# Schematic_MASTER.net
KiCad netlist of a schematic drawn in Altium Designer
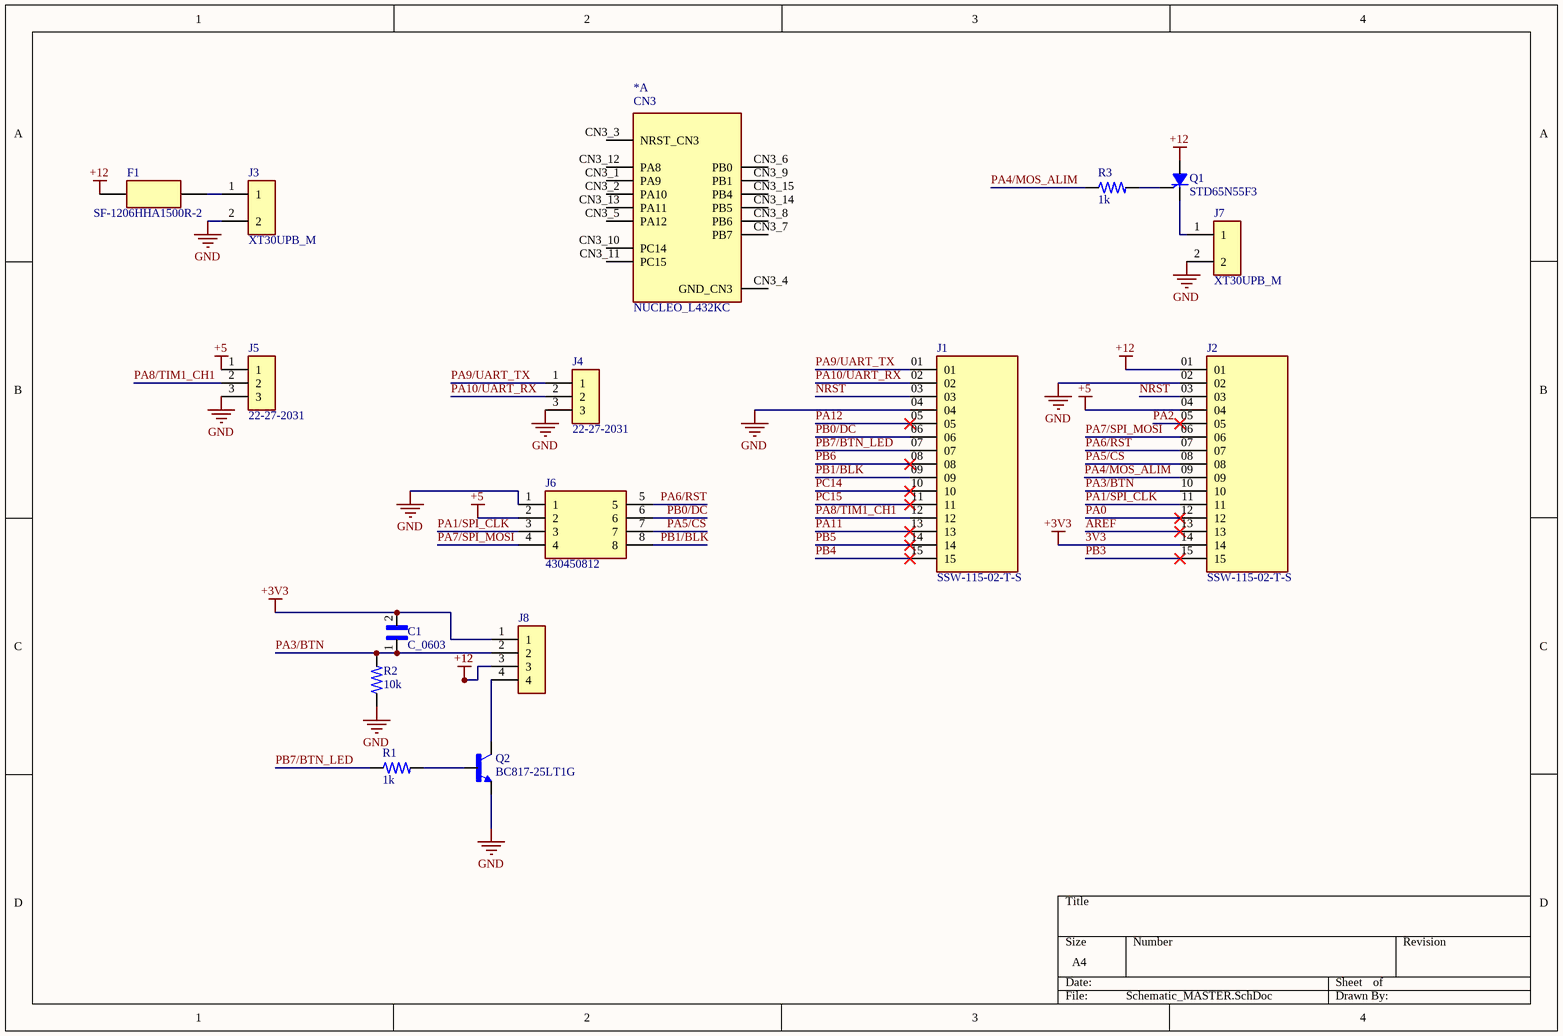
[diagram p0: Schematic_MASTER.SchDoc]

(export (version "E")
  (design (tool "Eeschema 10.0.6"))
  (components
    (comp (ref "*")
      (value "NUCLEO_L432KC")
      (footprint "NUCLEO_L432KC")
      (libsource (lib "Librairy_schematic") (part "NUCLEO_L432KC"))
    )
    (comp (ref "C1")
      (value "C_0603")
      (footprint "C_0603")
      (description "SMD capacitor 0603")
      (libsource (lib "Librairy_schematic") (part "C_0603"))
    )
    (comp (ref "F1")
      (value "SF-1206HHA1500R-2")
      (footprint "SF-1206HHA1500R-2")
      (libsource (lib "Librairy_schematic") (part "SF-1206HHA1500R-2"))
    )
    (comp (ref "J1")
      (value "SSW-115-02-T-S")
      (footprint "SSW-115-02-T-S")
      (libsource (lib "Librairy_schematic") (part "SSW-115-02-T-S"))
    )
    (comp (ref "J2")
      (value "SSW-115-02-T-S")
      (footprint "SSW-115-02-T-S")
      (libsource (lib "Librairy_schematic") (part "SSW-115-02-T-S"))
    )
    (comp (ref "J3")
      (value "XT30UPB_M")
      (footprint "XT30UPB-M")
      (libsource (lib "Librairy_schematic") (part "XT30UPB_M"))
    )
    (comp (ref "J4")
      (value "22-27-2031")
      (footprint "22-27-2031")
      (libsource (lib "Librairy_schematic") (part "22-27-2031"))
    )
    (comp (ref "J5")
      (value "22-27-2031")
      (footprint "22-27-2031")
      (libsource (lib "Librairy_schematic") (part "22-27-2031"))
    )
    (comp (ref "J6")
      (value "430450812")
      (footprint "430450812")
      (libsource (lib "Librairy_schematic") (part "430450812"))
    )
    (comp (ref "J7")
      (value "XT30UPB_M")
      (footprint "XT30UPB-M")
      (libsource (lib "Librairy_schematic") (part "XT30UPB_M"))
    )
    (comp (ref "J8")
      (value "22-27-2041")
      (footprint "22-27-2041")
      (libsource (lib "Librairy_schematic") (part "22-27-2041"))
    )
    (comp (ref "Q1")
      (value "STD65N55F3")
      (footprint "STD65N55F3")
      (libsource (lib "Librairy_schematic") (part "STD65N55F3"))
    )
    (comp (ref "Q2")
      (value "BC817-25LT1G")
      (footprint "SOT_BC817")
      (description "Transistor NPN 45V 0.5A hfe160 SOT23 ¦ ON Semiconductor BC817-25LT1G")
      (fields (field (name "MF") "ON Semiconductor"))
      (libsource (lib "Librairy_schematic") (part "BC817-25LT1G"))
    )
    (comp (ref "R1")
      (value "1k")
      (footprint "R_0603")
      (description "Res 0603")
      (libsource (lib "Librairy_schematic") (part "R_0603"))
    )
    (comp (ref "R2")
      (value "10k")
      (footprint "R_0603")
      (description "Res 0603")
      (libsource (lib "Librairy_schematic") (part "R_0603"))
    )
    (comp (ref "R3")
      (value "1k")
      (footprint "R_0603")
      (description "Res 0603")
      (libsource (lib "Librairy_schematic") (part "R_0603"))
    )
  )
  (nets
    (net (code "1") (name "+3V3") (class "Default")
      (node (ref "C1") (pin "2") (pinfunction "2_2") (pintype "passive"))
      (node (ref "J2") (pin "14") (pinfunction "14_14") (pintype "passive"))
      (node (ref "J8") (pin "1") (pinfunction "1_1") (pintype "passive"))
    )
    (net (code "2") (name "+5") (class "Default")
      (node (ref "J2") (pin "04") (pinfunction "04_04") (pintype "passive"))
      (node (ref "J5") (pin "1") (pinfunction "1_1") (pintype "passive"))
      (node (ref "J6") (pin "2") (pinfunction "2_2") (pintype "passive"))
    )
    (net (code "3") (name "+12") (class "Default")
      (node (ref "F1") (pin "1") (pinfunction "1_1") (pintype "passive"))
      (node (ref "J2") (pin "01") (pinfunction "01_01") (pintype "passive"))
      (node (ref "J8") (pin "3") (pinfunction "3_3") (pintype "passive"))
      (node (ref "Q1") (pin "2") (pinfunction "A_2") (pintype "passive"))
    )
    (net (code "4") (name "/AREF") (class "Default")
      (node (ref "J2") (pin "13") (pinfunction "13_13") (pintype "passive+no_connect"))
    )
    (net (code "5") (name "/NRST") (class "Default")
      (node (ref "J1") (pin "03") (pinfunction "03_03") (pintype "passive"))
      (node (ref "J2") (pin "03") (pinfunction "03_03") (pintype "passive"))
    )
    (net (code "6") (name "/PA0") (class "Default")
      (node (ref "J2") (pin "12") (pinfunction "12_12") (pintype "passive+no_connect"))
    )
    (net (code "7") (name "/PA1{slash}SPI_CLK") (class "Default")
      (node (ref "J2") (pin "11") (pinfunction "11_11") (pintype "passive"))
      (node (ref "J6") (pin "3") (pinfunction "3_3") (pintype "passive"))
    )
    (net (code "8") (name "/PA2") (class "Default")
      (node (ref "J2") (pin "05") (pinfunction "05_05") (pintype "passive+no_connect"))
    )
    (net (code "9") (name "/PA3{slash}BTN") (class "Default")
      (node (ref "C1") (pin "1") (pinfunction "1_1") (pintype "passive"))
      (node (ref "J2") (pin "10") (pinfunction "10_10") (pintype "passive"))
      (node (ref "J8") (pin "2") (pinfunction "2_2") (pintype "passive"))
      (node (ref "R2") (pin "2") (pinfunction "2_2") (pintype "passive"))
    )
    (net (code "10") (name "/PA4{slash}MOS_ALIM") (class "Default")
      (node (ref "J2") (pin "09") (pinfunction "09_09") (pintype "passive"))
      (node (ref "R3") (pin "1") (pinfunction "1_1") (pintype "passive"))
    )
    (net (code "11") (name "/PA5{slash}CS") (class "Default")
      (node (ref "J2") (pin "08") (pinfunction "08_08") (pintype "passive"))
      (node (ref "J6") (pin "7") (pinfunction "7_7") (pintype "passive"))
    )
    (net (code "12") (name "/PA6{slash}RST") (class "Default")
      (node (ref "J2") (pin "07") (pinfunction "07_07") (pintype "passive"))
      (node (ref "J6") (pin "5") (pinfunction "5_5") (pintype "passive"))
    )
    (net (code "13") (name "/PA7{slash}SPI_MOSI") (class "Default")
      (node (ref "J2") (pin "06") (pinfunction "06_06") (pintype "passive"))
      (node (ref "J6") (pin "4") (pinfunction "4_4") (pintype "passive"))
    )
    (net (code "14") (name "/PA8{slash}TIM1_CH1") (class "Default")
      (node (ref "J1") (pin "12") (pinfunction "12_12") (pintype "passive"))
      (node (ref "J5") (pin "2") (pinfunction "2_2") (pintype "passive"))
    )
    (net (code "15") (name "/PA9{slash}UART_TX") (class "Default")
      (node (ref "J1") (pin "01") (pinfunction "01_01") (pintype "passive"))
      (node (ref "J4") (pin "1") (pinfunction "1_1") (pintype "passive"))
    )
    (net (code "16") (name "/PA10{slash}UART_RX") (class "Default")
      (node (ref "J1") (pin "02") (pinfunction "02_02") (pintype "passive"))
      (node (ref "J4") (pin "2") (pinfunction "2_2") (pintype "passive"))
    )
    (net (code "17") (name "/PA11") (class "Default")
      (node (ref "J1") (pin "13") (pinfunction "13_13") (pintype "passive+no_connect"))
    )
    (net (code "18") (name "/PA12") (class "Default")
      (node (ref "J1") (pin "05") (pinfunction "05_05") (pintype "passive+no_connect"))
    )
    (net (code "19") (name "/PB0{slash}DC") (class "Default")
      (node (ref "J1") (pin "06") (pinfunction "06_06") (pintype "passive"))
      (node (ref "J6") (pin "6") (pinfunction "6_6") (pintype "passive"))
    )
    (net (code "20") (name "/PB1{slash}BLK") (class "Default")
      (node (ref "J1") (pin "09") (pinfunction "09_09") (pintype "passive"))
      (node (ref "J6") (pin "8") (pinfunction "8_8") (pintype "passive"))
    )
    (net (code "21") (name "/PB3") (class "Default")
      (node (ref "J2") (pin "15") (pinfunction "15_15") (pintype "passive+no_connect"))
    )
    (net (code "22") (name "/PB4") (class "Default")
      (node (ref "J1") (pin "15") (pinfunction "15_15") (pintype "passive+no_connect"))
    )
    (net (code "23") (name "/PB5") (class "Default")
      (node (ref "J1") (pin "14") (pinfunction "14_14") (pintype "passive+no_connect"))
    )
    (net (code "24") (name "/PB6") (class "Default")
      (node (ref "J1") (pin "08") (pinfunction "08_08") (pintype "passive+no_connect"))
    )
    (net (code "25") (name "/PB7{slash}BTN_LED") (class "Default")
      (node (ref "J1") (pin "07") (pinfunction "07_07") (pintype "passive"))
      (node (ref "R1") (pin "1") (pinfunction "1_1") (pintype "passive"))
    )
    (net (code "26") (name "/PC14") (class "Default")
      (node (ref "J1") (pin "10") (pinfunction "10_10") (pintype "passive+no_connect"))
    )
    (net (code "27") (name "/PC15") (class "Default")
      (node (ref "J1") (pin "11") (pinfunction "11_11") (pintype "passive+no_connect"))
    )
    (net (code "28") (name "GND") (class "Default")
      (node (ref "J1") (pin "04") (pinfunction "04_04") (pintype "passive"))
      (node (ref "J2") (pin "02") (pinfunction "02_02") (pintype "passive"))
      (node (ref "J3") (pin "2") (pinfunction "2_2") (pintype "passive"))
      (node (ref "J4") (pin "3") (pinfunction "3_3") (pintype "passive"))
      (node (ref "J5") (pin "3") (pinfunction "3_3") (pintype "passive"))
      (node (ref "J6") (pin "1") (pinfunction "1_1") (pintype "passive"))
      (node (ref "J7") (pin "2") (pinfunction "2_2") (pintype "passive"))
      (node (ref "Q2") (pin "2") (pinfunction "E_2") (pintype "passive"))
      (node (ref "R2") (pin "1") (pinfunction "1_1") (pintype "passive"))
    )
    (net (code "29") (name "Net-(F1-Pad2)") (class "Default")
      (node (ref "F1") (pin "2") (pinfunction "2_2") (pintype "passive"))
      (node (ref "J3") (pin "1") (pinfunction "1_1") (pintype "passive"))
    )
    (net (code "30") (name "Net-(Q1-G)") (class "Default")
      (node (ref "Q1") (pin "1") (pinfunction "G_1") (pintype "passive"))
      (node (ref "R3") (pin "2") (pinfunction "2_2") (pintype "passive"))
    )
    (net (code "31") (name "Net-(Q1-K)") (class "Default")
      (node (ref "J7") (pin "1") (pinfunction "1_1") (pintype "passive"))
      (node (ref "Q1") (pin "3") (pinfunction "K_3") (pintype "passive"))
    )
    (net (code "32") (name "Net-(Q2-B)") (class "Default")
      (node (ref "Q2") (pin "1") (pinfunction "B_1") (pintype "passive"))
      (node (ref "R1") (pin "2") (pinfunction "2_2") (pintype "passive"))
    )
    (net (code "33") (name "Net-(Q2-C)") (class "Default")
      (node (ref "J8") (pin "4") (pinfunction "4_4") (pintype "passive"))
      (node (ref "Q2") (pin "3") (pinfunction "C_3") (pintype "passive"))
    )
    (net (code "34") (name "unconnected-(*A-GND_CN3-PadCN3_4)") (class "Default")
      (node (ref "*") (pin "CN3_4") (pinfunction "GND_CN3_CN3_4") (pintype "passive"))
    )
    (net (code "35") (name "unconnected-(*A-NRST_CN3-PadCN3_3)") (class "Default")
      (node (ref "*") (pin "CN3_3") (pinfunction "NRST_CN3_CN3_3") (pintype "passive"))
    )
    (net (code "36") (name "unconnected-(*A-PA8-PadCN3_12)") (class "Default")
      (node (ref "*") (pin "CN3_12") (pinfunction "PA8_CN3_12") (pintype "passive"))
    )
    (net (code "37") (name "unconnected-(*A-PA9-PadCN3_1)") (class "Default")
      (node (ref "*") (pin "CN3_1") (pinfunction "PA9_CN3_1") (pintype "passive"))
    )
    (net (code "38") (name "unconnected-(*A-PA10-PadCN3_2)") (class "Default")
      (node (ref "*") (pin "CN3_2") (pinfunction "PA10_CN3_2") (pintype "passive"))
    )
    (net (code "39") (name "unconnected-(*A-PA11-PadCN3_13)") (class "Default")
      (node (ref "*") (pin "CN3_13") (pinfunction "PA11_CN3_13") (pintype "passive"))
    )
    (net (code "40") (name "unconnected-(*A-PA12-PadCN3_5)") (class "Default")
      (node (ref "*") (pin "CN3_5") (pinfunction "PA12_CN3_5") (pintype "passive"))
    )
    (net (code "41") (name "unconnected-(*A-PB0-PadCN3_6)") (class "Default")
      (node (ref "*") (pin "CN3_6") (pinfunction "PB0_CN3_6") (pintype "passive"))
    )
    (net (code "42") (name "unconnected-(*A-PB1-PadCN3_9)") (class "Default")
      (node (ref "*") (pin "CN3_9") (pinfunction "PB1_CN3_9") (pintype "passive"))
    )
    (net (code "43") (name "unconnected-(*A-PB4-PadCN3_15)") (class "Default")
      (node (ref "*") (pin "CN3_15") (pinfunction "PB4_CN3_15") (pintype "passive"))
    )
    (net (code "44") (name "unconnected-(*A-PB5-PadCN3_14)") (class "Default")
      (node (ref "*") (pin "CN3_14") (pinfunction "PB5_CN3_14") (pintype "passive"))
    )
    (net (code "45") (name "unconnected-(*A-PB6-PadCN3_8)") (class "Default")
      (node (ref "*") (pin "CN3_8") (pinfunction "PB6_CN3_8") (pintype "passive"))
    )
    (net (code "46") (name "unconnected-(*A-PB7-PadCN3_7)") (class "Default")
      (node (ref "*") (pin "CN3_7") (pinfunction "PB7_CN3_7") (pintype "passive"))
    )
    (net (code "47") (name "unconnected-(*A-PC14-PadCN3_10)") (class "Default")
      (node (ref "*") (pin "CN3_10") (pinfunction "PC14_CN3_10") (pintype "passive"))
    )
    (net (code "48") (name "unconnected-(*A-PC15-PadCN3_11)") (class "Default")
      (node (ref "*") (pin "CN3_11") (pinfunction "PC15_CN3_11") (pintype "passive"))
    )
  )
)
